# Module01.net
KiCad netlist of a schematic drawn in Altium Designer
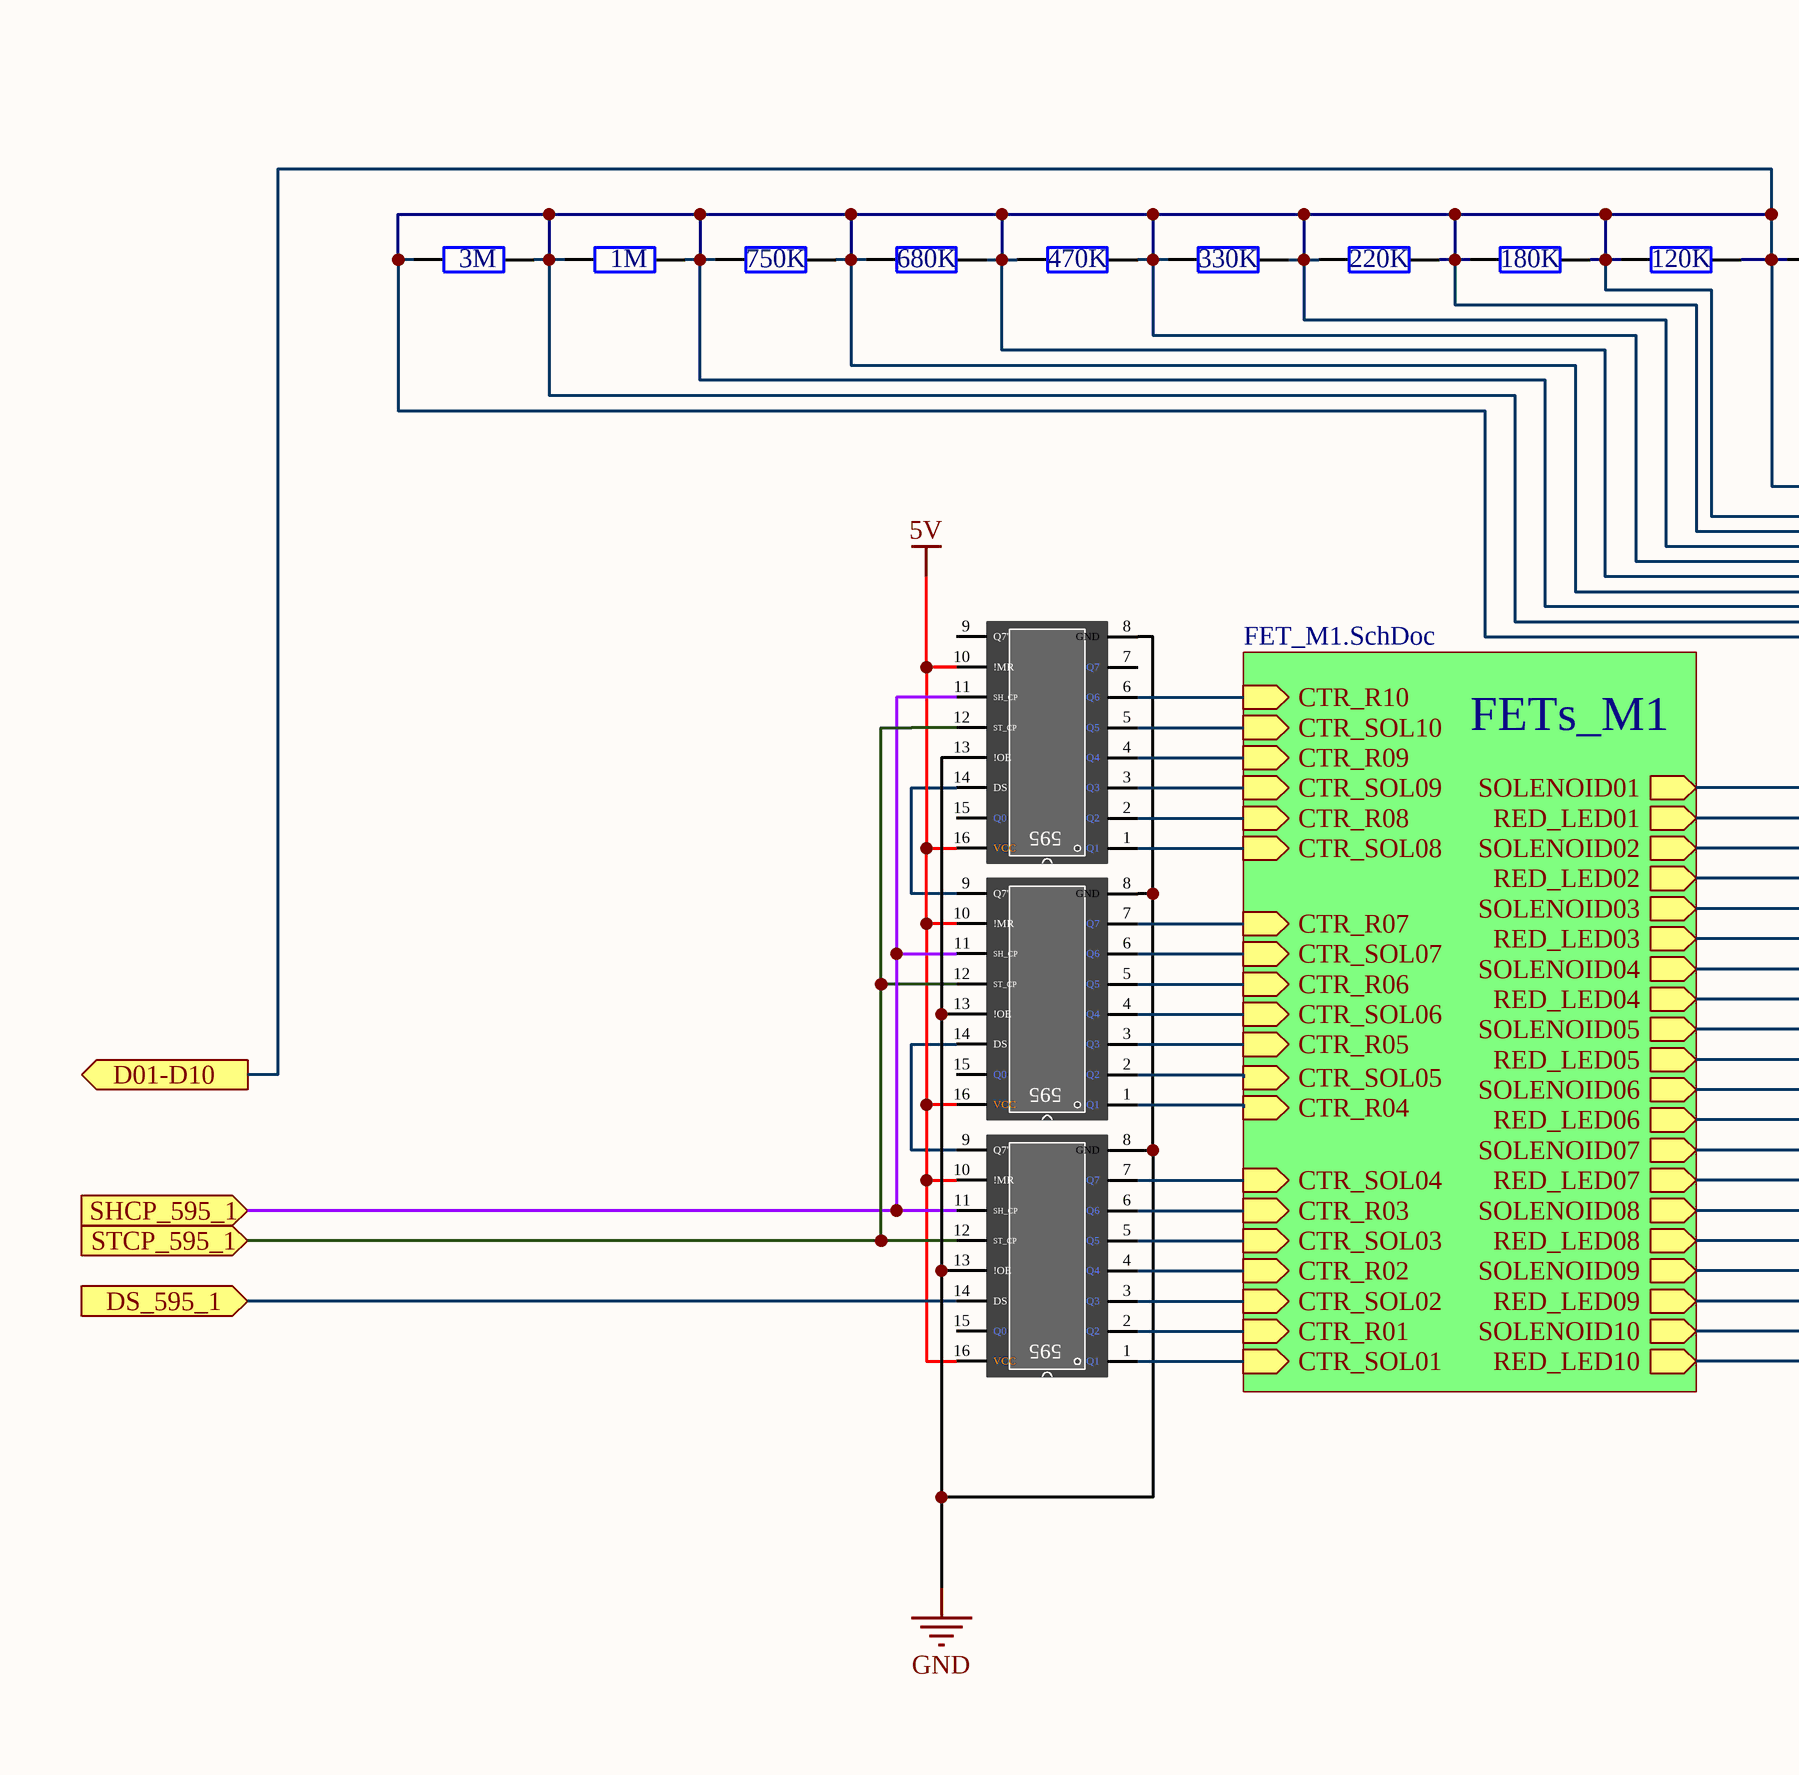
[diagram p0: Module01.SchDoc, left]
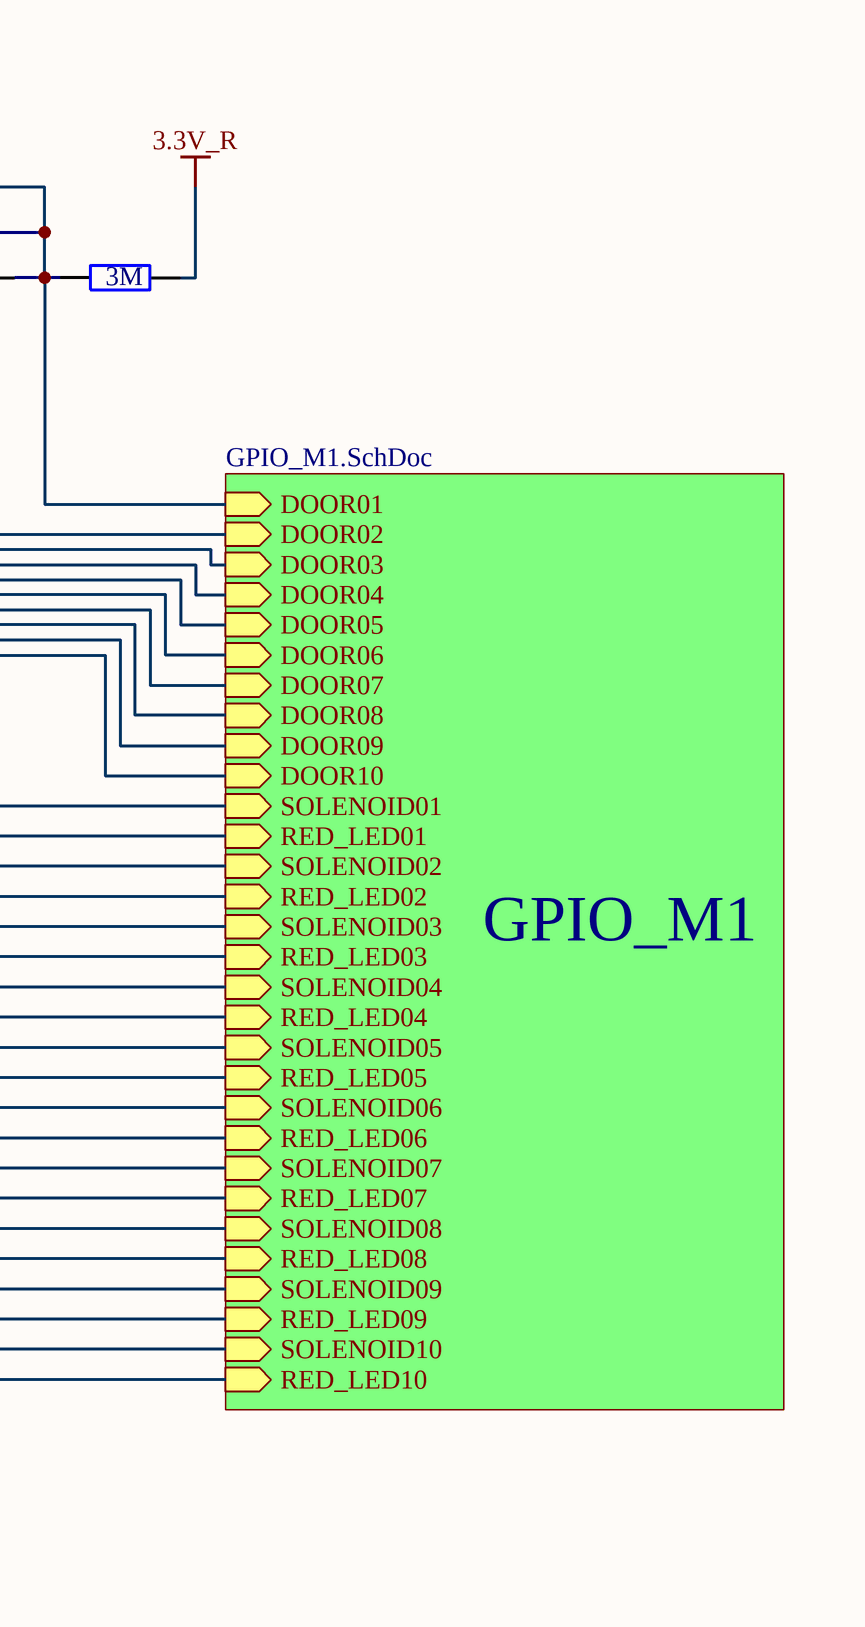
[diagram p1: Module01.SchDoc, right]

(export (version "E")
  (design (tool "Eeschema 10.0.6"))
  (components
    (comp (ref "1") (value "5#HC74595") (footprint "5#HC74595") (libsource (lib "Sch") (part "5#HC74595")))
    (comp (ref "2") (value "5#HC74595") (footprint "5#HC74595") (libsource (lib "Sch") (part "5#HC74595")))
    (comp (ref "3") (value "5#HC74595") (footprint "5#HC74595") (libsource (lib "Sch") (part "5#HC74595")))
    (comp (ref "R1")
      (value "3M")
      (footprint "AXIAL-0.4")
      (description "Resistor")
      (fields (field (name "PUBLISHER") "Altium Limited"))
      (libsource (lib "Miscellaneous Devices") (part "Res2"))
    )
    (comp (ref "R2")
      (value "1M")
      (footprint "AXIAL-0.4")
      (description "Resistor")
      (fields (field (name "PUBLISHER") "Altium Limited"))
      (libsource (lib "Miscellaneous Devices") (part "Res2"))
    )
    (comp (ref "R3")
      (value "750K")
      (footprint "AXIAL-0.4")
      (description "Resistor")
      (fields (field (name "PUBLISHER") "Altium Limited"))
      (libsource (lib "Miscellaneous Devices") (part "Res2"))
    )
    (comp (ref "R4")
      (value "680K")
      (footprint "AXIAL-0.4")
      (description "Resistor")
      (fields (field (name "PUBLISHER") "Altium Limited"))
      (libsource (lib "Miscellaneous Devices") (part "Res2"))
    )
    (comp (ref "R5")
      (value "470K")
      (footprint "AXIAL-0.4")
      (description "Resistor")
      (fields (field (name "PUBLISHER") "Altium Limited"))
      (libsource (lib "Miscellaneous Devices") (part "Res2"))
    )
    (comp (ref "R6")
      (value "330K")
      (footprint "AXIAL-0.4")
      (description "Resistor")
      (fields (field (name "PUBLISHER") "Altium Limited"))
      (libsource (lib "Miscellaneous Devices") (part "Res2"))
    )
    (comp (ref "R7")
      (value "220K")
      (footprint "AXIAL-0.4")
      (description "Resistor")
      (fields (field (name "PUBLISHER") "Altium Limited"))
      (libsource (lib "Miscellaneous Devices") (part "Res2"))
    )
    (comp (ref "R8")
      (value "180K")
      (footprint "AXIAL-0.4")
      (description "Resistor")
      (fields (field (name "PUBLISHER") "Altium Limited"))
      (libsource (lib "Miscellaneous Devices") (part "Res2"))
    )
    (comp (ref "R9")
      (value "120K")
      (footprint "AXIAL-0.4")
      (description "Resistor")
      (fields (field (name "PUBLISHER") "Altium Limited"))
      (libsource (lib "Miscellaneous Devices") (part "Res2"))
    )
    (comp (ref "R10")
      (value "3M")
      (footprint "AXIAL-0.4")
      (description "Resistor")
      (fields (field (name "PUBLISHER") "Altium Limited"))
      (libsource (lib "Miscellaneous Devices") (part "Res2"))
    )
  )
  (nets
    (net (code "1") (name "/CTR_R01") (class "Default")
      (node (ref "1") (pin "2") (pinfunction "Q2_2") (pintype "passive"))
    )
    (net (code "2") (name "/CTR_R02") (class "Default")
      (node (ref "1") (pin "4") (pinfunction "Q4_4") (pintype "passive"))
    )
    (net (code "3") (name "/CTR_R03") (class "Default")
      (node (ref "1") (pin "6") (pinfunction "Q6_6") (pintype "passive"))
    )
    (net (code "4") (name "/CTR_R04") (class "Default")
      (node (ref "2") (pin "1") (pinfunction "Q1_1") (pintype "passive"))
    )
    (net (code "5") (name "/CTR_R05") (class "Default")
      (node (ref "2") (pin "3") (pinfunction "Q3_3") (pintype "passive"))
    )
    (net (code "6") (name "/CTR_R06") (class "Default")
      (node (ref "2") (pin "5") (pinfunction "Q5_5") (pintype "passive"))
    )
    (net (code "7") (name "/CTR_R07") (class "Default")
      (node (ref "2") (pin "7") (pinfunction "Q7_7") (pintype "passive"))
    )
    (net (code "8") (name "/CTR_R08") (class "Default")
      (node (ref "3") (pin "2") (pinfunction "Q2_2") (pintype "passive"))
    )
    (net (code "9") (name "/CTR_R09") (class "Default")
      (node (ref "3") (pin "4") (pinfunction "Q4_4") (pintype "passive"))
    )
    (net (code "10") (name "/CTR_R10") (class "Default")
      (node (ref "3") (pin "6") (pinfunction "Q6_6") (pintype "passive"))
    )
    (net (code "11") (name "/CTR_SOL01") (class "Default")
      (node (ref "1") (pin "1") (pinfunction "Q1_1") (pintype "passive"))
    )
    (net (code "12") (name "/CTR_SOL02") (class "Default")
      (node (ref "1") (pin "3") (pinfunction "Q3_3") (pintype "passive"))
    )
    (net (code "13") (name "/CTR_SOL03") (class "Default")
      (node (ref "1") (pin "5") (pinfunction "Q5_5") (pintype "passive"))
    )
    (net (code "14") (name "/CTR_SOL04") (class "Default")
      (node (ref "1") (pin "7") (pinfunction "Q7_7") (pintype "passive"))
    )
    (net (code "15") (name "/CTR_SOL05") (class "Default")
      (node (ref "2") (pin "2") (pinfunction "Q2_2") (pintype "passive"))
    )
    (net (code "16") (name "/CTR_SOL06") (class "Default")
      (node (ref "2") (pin "4") (pinfunction "Q4_4") (pintype "passive"))
    )
    (net (code "17") (name "/CTR_SOL07") (class "Default")
      (node (ref "2") (pin "6") (pinfunction "Q6_6") (pintype "passive"))
    )
    (net (code "18") (name "/CTR_SOL08") (class "Default")
      (node (ref "3") (pin "1") (pinfunction "Q1_1") (pintype "passive"))
    )
    (net (code "19") (name "/CTR_SOL09") (class "Default")
      (node (ref "3") (pin "3") (pinfunction "Q3_3") (pintype "passive"))
    )
    (net (code "20") (name "/CTR_SOL10") (class "Default")
      (node (ref "3") (pin "5") (pinfunction "Q5_5") (pintype "passive"))
    )
    (net (code "21") (name "/D01-D10") (class "Default")
      (node (ref "R1") (pin "1") (pinfunction "1_1") (pintype "passive"))
      (node (ref "R1") (pin "2") (pinfunction "2_2") (pintype "passive"))
      (node (ref "R10") (pin "2") (pinfunction "2_2") (pintype "passive"))
      (node (ref "R2") (pin "1") (pinfunction "1_1") (pintype "passive"))
      (node (ref "R2") (pin "2") (pinfunction "2_2") (pintype "passive"))
      (node (ref "R3") (pin "1") (pinfunction "1_1") (pintype "passive"))
      (node (ref "R3") (pin "2") (pinfunction "2_2") (pintype "passive"))
      (node (ref "R4") (pin "1") (pinfunction "1_1") (pintype "passive"))
      (node (ref "R4") (pin "2") (pinfunction "2_2") (pintype "passive"))
      (node (ref "R5") (pin "1") (pinfunction "1_1") (pintype "passive"))
      (node (ref "R5") (pin "2") (pinfunction "2_2") (pintype "passive"))
      (node (ref "R6") (pin "1") (pinfunction "1_1") (pintype "passive"))
      (node (ref "R6") (pin "2") (pinfunction "2_2") (pintype "passive"))
      (node (ref "R7") (pin "1") (pinfunction "1_1") (pintype "passive"))
      (node (ref "R7") (pin "2") (pinfunction "2_2") (pintype "passive"))
      (node (ref "R8") (pin "1") (pinfunction "1_1") (pintype "passive"))
      (node (ref "R8") (pin "2") (pinfunction "2_2") (pintype "passive"))
      (node (ref "R9") (pin "1") (pinfunction "1_1") (pintype "passive"))
      (node (ref "R9") (pin "2") (pinfunction "2_2") (pintype "passive"))
    )
    (net (code "22") (name "/DS_595_1") (class "Default")
      (node (ref "1") (pin "14") (pinfunction "DS_14") (pintype "passive"))
    )
    (net (code "33") (name "/SHCP_595_1") (class "Default")
      (node (ref "1") (pin "11") (pinfunction "SH_CP_11") (pintype "passive"))
      (node (ref "2") (pin "11") (pinfunction "SH_CP_11") (pintype "passive"))
      (node (ref "3") (pin "11") (pinfunction "SH_CP_11") (pintype "passive"))
    )
    (net (code "44") (name "/STCP_595_1") (class "Default")
      (node (ref "1") (pin "12") (pinfunction "ST_CP_12") (pintype "passive"))
      (node (ref "2") (pin "12") (pinfunction "ST_CP_12") (pintype "passive"))
      (node (ref "3") (pin "12") (pinfunction "ST_CP_12") (pintype "passive"))
    )
    (net (code "45") (name "3.3V_R") (class "Default")
      (node (ref "R10") (pin "1") (pinfunction "1_1") (pintype "passive"))
    )
    (net (code "46") (name "5V") (class "Default")
      (node (ref "1") (pin "10") (pinfunction "!MR_10") (pintype "passive"))
      (node (ref "1") (pin "16") (pinfunction "VCC_16") (pintype "passive"))
      (node (ref "2") (pin "10") (pinfunction "!MR_10") (pintype "passive"))
      (node (ref "2") (pin "16") (pinfunction "VCC_16") (pintype "passive"))
      (node (ref "3") (pin "10") (pinfunction "!MR_10") (pintype "passive"))
      (node (ref "3") (pin "16") (pinfunction "VCC_16") (pintype "passive"))
    )
    (net (code "47") (name "GND") (class "Default")
      (node (ref "1") (pin "13") (pinfunction "!OE_13") (pintype "passive"))
      (node (ref "1") (pin "8") (pinfunction "GND_8") (pintype "passive"))
      (node (ref "2") (pin "13") (pinfunction "!OE_13") (pintype "passive"))
      (node (ref "2") (pin "8") (pinfunction "GND_8") (pintype "passive"))
      (node (ref "3") (pin "13") (pinfunction "!OE_13") (pintype "passive"))
      (node (ref "3") (pin "8") (pinfunction "GND_8") (pintype "passive"))
    )
    (net (code "48") (name "Net-(1-Q7')") (class "Default")
      (node (ref "1") (pin "9") (pinfunction "Q7'_9") (pintype "passive"))
      (node (ref "2") (pin "14") (pinfunction "DS_14") (pintype "passive"))
    )
    (net (code "49") (name "Net-(2-Q7')") (class "Default")
      (node (ref "2") (pin "9") (pinfunction "Q7'_9") (pintype "passive"))
      (node (ref "3") (pin "14") (pinfunction "DS_14") (pintype "passive"))
    )
    (net (code "50") (name "unconnected-(1-Q0-Pad15)") (class "Default")
      (node (ref "1") (pin "15") (pinfunction "Q0_15") (pintype "passive"))
    )
    (net (code "51") (name "unconnected-(2-Q0-Pad15)") (class "Default")
      (node (ref "2") (pin "15") (pinfunction "Q0_15") (pintype "passive"))
    )
    (net (code "52") (name "unconnected-(3-Q0-Pad15)") (class "Default")
      (node (ref "3") (pin "15") (pinfunction "Q0_15") (pintype "passive"))
    )
    (net (code "53") (name "unconnected-(3-Q7'-Pad9)") (class "Default")
      (node (ref "3") (pin "9") (pinfunction "Q7'_9") (pintype "passive"))
    )
    (net (code "54") (name "unconnected-(3-Q7-Pad7)") (class "Default")
      (node (ref "3") (pin "7") (pinfunction "Q7_7") (pintype "passive"))
    )
  )
)
